# power_supply.net
KiCad netlist of a schematic drawn in EAGLE
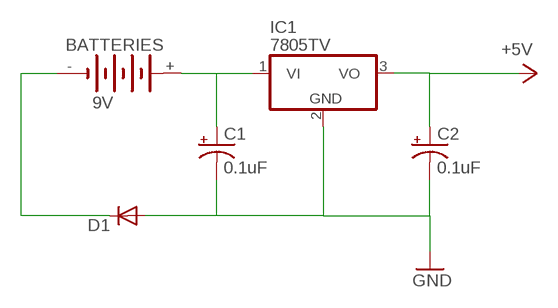
[diagram p0: schematic, sheet 1]

(export (version "E")
  (design (tool "Eeschema 10.0.6"))
  (components
    (comp (ref "BATTERIES")
      (value "VMS4V8")
      (footprint "eagle-import:VMS4V8")
      (fields (field (name "VOLTAGE") "9V"))
      (libsource (lib "eagle-import") (part "VMS4V8"))
    )
    (comp (ref "C1")
      (value "0.1uF")
      (footprint "eagle-import:085CS_1AW")
      (libsource (lib "eagle-import") (part "CPOL-US085CS-1AW"))
    )
    (comp (ref "C2")
      (value "0.1uF")
      (footprint "eagle-import:085CS_1AW")
      (libsource (lib "eagle-import") (part "CPOL-US085CS-1AW"))
    )
    (comp (ref "D1")
      (value "1N4007")
      (footprint "eagle-import:1N4007STANDING")
      (libsource (lib "eagle-import") (part "1N4007"))
    )
    (comp (ref "IC1")
      (value "7805TV")
      (footprint "eagle-import:TO220V")
      (libsource (lib "eagle-import") (part "78TV05"))
    )
  )
  (nets
    (net (code "1") (name "+5V") (class "Default")
      (node (ref "C2") (pin "+") (pinfunction "+_+") (pintype "passive"))
      (node (ref "IC1") (pin "3") (pinfunction "VO_3") (pintype "passive"))
    )
    (net (code "2") (name "GND") (class "Default")
      (node (ref "C1") (pin "-") (pinfunction "-_-") (pintype "passive"))
      (node (ref "C2") (pin "-") (pinfunction "-_-") (pintype "passive"))
      (node (ref "D1") (pin "A") (pinfunction "A_A") (pintype "passive"))
      (node (ref "IC1") (pin "2") (pinfunction "GND_2") (pintype "passive"))
    )
    (net (code "3") (name "Net-(BATTERIES-Pad-)") (class "Default")
      (node (ref "BATTERIES") (pin "-") (pinfunction "-_-") (pintype "passive"))
      (node (ref "D1") (pin "C") (pinfunction "C_C") (pintype "passive"))
    )
    (net (code "4") (name "Net-(IC1-VI)") (class "Default")
      (node (ref "BATTERIES") (pin "+") (pinfunction "+_+") (pintype "passive"))
      (node (ref "C1") (pin "+") (pinfunction "+_+") (pintype "passive"))
      (node (ref "IC1") (pin "1") (pinfunction "VI_1") (pintype "input"))
    )
  )
)
